# INTERFACE.net
KiCad netlist of a schematic drawn in EAGLE
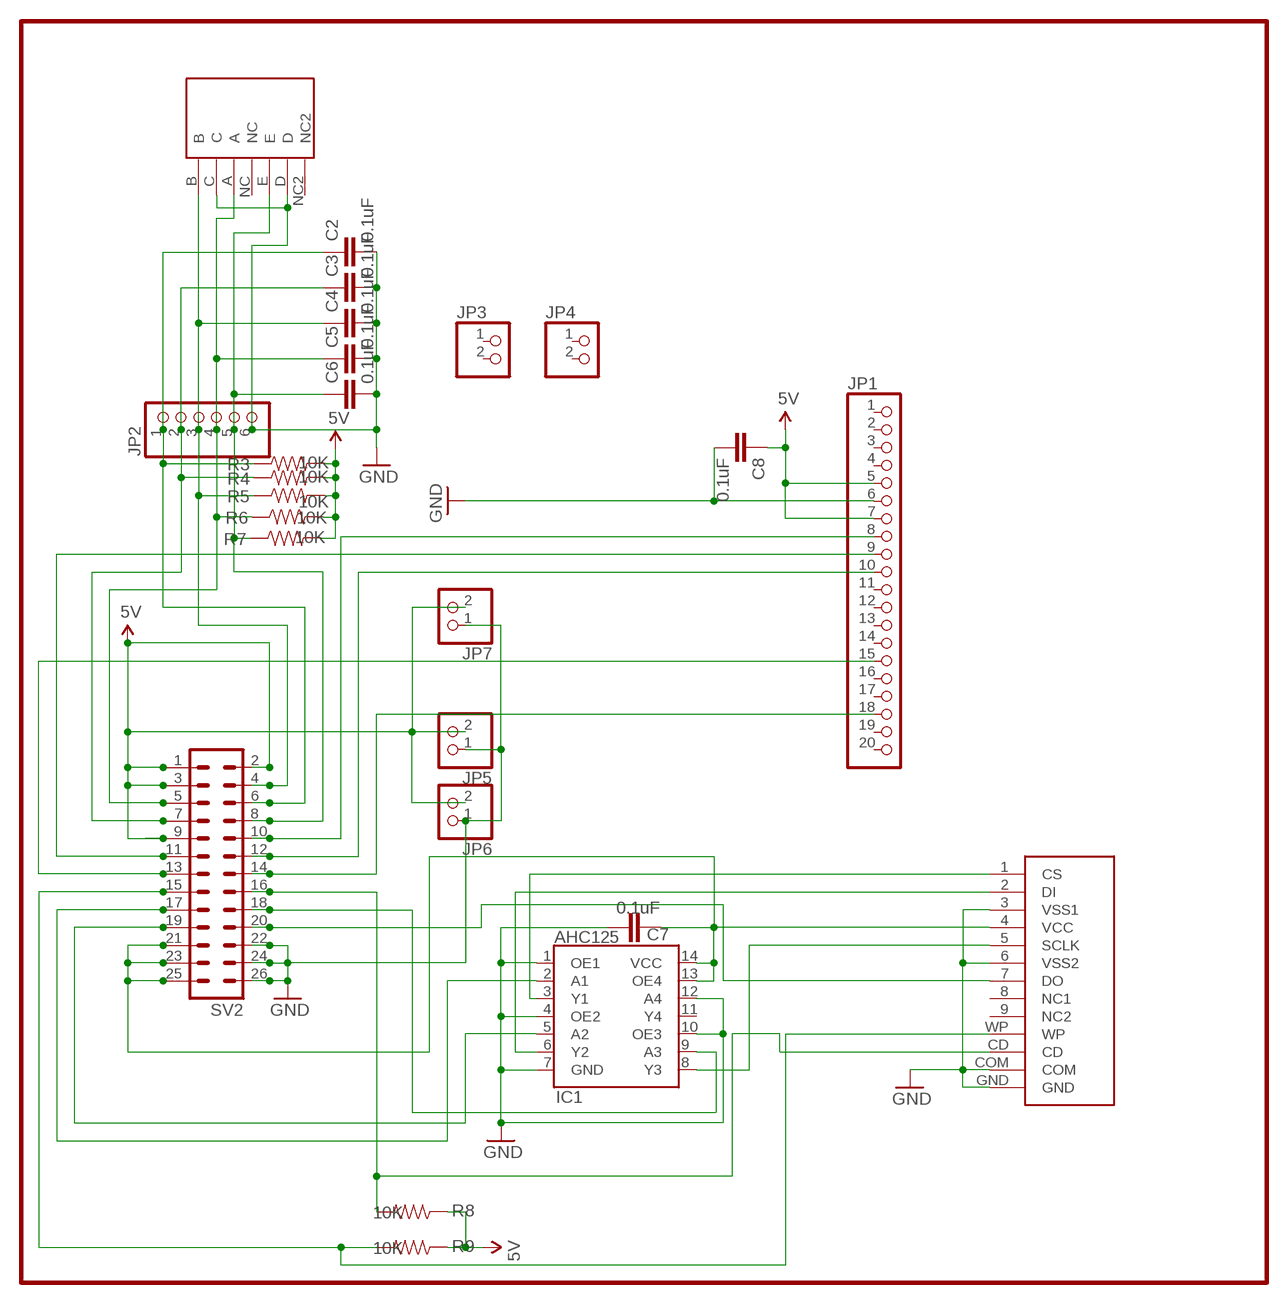
[diagram p0: schematic, sheet 1]

(export (version "E")
  (design (tool "Eeschema 10.0.6"))
  (components
    (comp (ref "C2")
      (value "0.1uF")
      (footprint "eagle-import:0805")
      (libsource (lib "eagle-import") (part "CAP0805"))
    )
    (comp (ref "C3")
      (value "0.1uF")
      (footprint "eagle-import:0805")
      (libsource (lib "eagle-import") (part "CAP0805"))
    )
    (comp (ref "C4")
      (value "0.1uF")
      (footprint "eagle-import:0805")
      (libsource (lib "eagle-import") (part "CAP0805"))
    )
    (comp (ref "C5")
      (value "0.1uF")
      (footprint "eagle-import:0805")
      (libsource (lib "eagle-import") (part "CAP0805"))
    )
    (comp (ref "C6")
      (value "0.1uF")
      (footprint "eagle-import:0805")
      (libsource (lib "eagle-import") (part "CAP0805"))
    )
    (comp (ref "C7")
      (value "0.1uF")
      (footprint "eagle-import:0805")
      (libsource (lib "eagle-import") (part "CAP0805"))
    )
    (comp (ref "C8")
      (value "0.1uF")
      (footprint "eagle-import:0805")
      (libsource (lib "eagle-import") (part "CAP0805"))
    )
    (comp (ref "IC1")
      (value "AHC125")
      (footprint "eagle-import:DIN14")
      (libsource (lib "eagle-import") (part "AHC125"))
    )
    (comp (ref "JP1")
      (value "PINHD-1X20")
      (footprint "eagle-import:1X20")
      (libsource (lib "eagle-import") (part "PINHD-1X20"))
    )
    (comp (ref "JP2")
      (value "PINHD-1X6")
      (footprint "eagle-import:1X06")
      (libsource (lib "eagle-import") (part "PINHD-1X6"))
    )
    (comp (ref "JP3")
      (value "PINHD-1X2")
      (footprint "eagle-import:1X02")
      (libsource (lib "eagle-import") (part "PINHD-1X2"))
    )
    (comp (ref "JP4")
      (value "PINHD-1X2")
      (footprint "eagle-import:1X02")
      (libsource (lib "eagle-import") (part "PINHD-1X2"))
    )
    (comp (ref "JP5")
      (value "PINHD-1X2")
      (footprint "eagle-import:1X02")
      (libsource (lib "eagle-import") (part "PINHD-1X2"))
    )
    (comp (ref "JP6")
      (value "PINHD-1X2")
      (footprint "eagle-import:1X02")
      (libsource (lib "eagle-import") (part "PINHD-1X2"))
    )
    (comp (ref "JP7")
      (value "PINHD-1X2")
      (footprint "eagle-import:1X02")
      (libsource (lib "eagle-import") (part "PINHD-1X2"))
    )
    (comp (ref "Q2")
      (value "SDCARD")
      (footprint "eagle-import:SDCARD")
      (libsource (lib "eagle-import") (part "SDCARD"))
    )
    (comp (ref "R3")
      (value "10K")
      (footprint "eagle-import:0805")
      (libsource (lib "eagle-import") (part "RESISTOR"))
    )
    (comp (ref "R4")
      (value "10K")
      (footprint "eagle-import:0805")
      (libsource (lib "eagle-import") (part "RESISTOR"))
    )
    (comp (ref "R5")
      (value "10K")
      (footprint "eagle-import:0805")
      (libsource (lib "eagle-import") (part "RESISTOR"))
    )
    (comp (ref "R6")
      (value "10K")
      (footprint "eagle-import:0805")
      (libsource (lib "eagle-import") (part "RESISTOR"))
    )
    (comp (ref "R7")
      (value "10K")
      (footprint "eagle-import:0805")
      (libsource (lib "eagle-import") (part "RESISTOR"))
    )
    (comp (ref "R8")
      (value "10K")
      (footprint "eagle-import:0805")
      (libsource (lib "eagle-import") (part "RESISTOR"))
    )
    (comp (ref "R9")
      (value "10K")
      (footprint "eagle-import:0805")
      (libsource (lib "eagle-import") (part "RESISTOR"))
    )
    (comp (ref "S2")
      (value "DJFS")
      (footprint "eagle-import:PIN5")
      (libsource (lib "eagle-import") (part "DJFS"))
    )
    (comp (ref "SV2")
      (value "ML26L")
      (footprint "eagle-import:ML26L")
      (libsource (lib "eagle-import") (part "ML26L"))
    )
  )
  (nets
    (net (code "1") (name "5V") (class "Default")
      (node (ref "C8") (pin "1") (pinfunction "1_1") (pintype "passive"))
      (node (ref "JP1") (pin "5") (pinfunction "5_5") (pintype "passive"))
      (node (ref "JP1") (pin "7") (pinfunction "7_7") (pintype "passive"))
      (node (ref "JP5") (pin "2") (pinfunction "2_2") (pintype "passive"))
      (node (ref "JP6") (pin "2") (pinfunction "2_2") (pintype "passive"))
      (node (ref "JP7") (pin "2") (pinfunction "2_2") (pintype "passive"))
      (node (ref "R3") (pin "2") (pinfunction "2_2") (pintype "passive"))
      (node (ref "R4") (pin "2") (pinfunction "2_2") (pintype "passive"))
      (node (ref "R5") (pin "2") (pinfunction "2_2") (pintype "passive"))
      (node (ref "R6") (pin "2") (pinfunction "2_2") (pintype "passive"))
      (node (ref "R7") (pin "2") (pinfunction "2_2") (pintype "passive"))
      (node (ref "R8") (pin "1") (pinfunction "1_1") (pintype "passive"))
      (node (ref "R9") (pin "1") (pinfunction "1_1") (pintype "passive"))
      (node (ref "SV2") (pin "1") (pinfunction "1_1") (pintype "passive"))
      (node (ref "SV2") (pin "2") (pinfunction "2_2") (pintype "passive"))
      (node (ref "SV2") (pin "3") (pinfunction "3_3") (pintype "passive"))
      (node (ref "SV2") (pin "9") (pinfunction "9_9") (pintype "passive"))
    )
    (net (code "2") (name "GND") (class "Default")
      (node (ref "C2") (pin "2") (pinfunction "2_2") (pintype "passive"))
      (node (ref "C3") (pin "2") (pinfunction "2_2") (pintype "passive"))
      (node (ref "C4") (pin "2") (pinfunction "2_2") (pintype "passive"))
      (node (ref "C5") (pin "2") (pinfunction "2_2") (pintype "passive"))
      (node (ref "C6") (pin "2") (pinfunction "2_2") (pintype "passive"))
      (node (ref "C7") (pin "2") (pinfunction "2_2") (pintype "passive"))
      (node (ref "C8") (pin "2") (pinfunction "2_2") (pintype "passive"))
      (node (ref "IC1") (pin "1") (pinfunction "OE1_1") (pintype "input"))
      (node (ref "IC1") (pin "10") (pinfunction "OE3_10") (pintype "input"))
      (node (ref "IC1") (pin "12") (pinfunction "A4_12") (pintype "input"))
      (node (ref "IC1") (pin "4") (pinfunction "OE2_4") (pintype "input"))
      (node (ref "IC1") (pin "7") (pinfunction "GND_7") (pintype "power_in"))
      (node (ref "JP1") (pin "6") (pinfunction "6_6") (pintype "passive"))
      (node (ref "JP2") (pin "6") (pinfunction "6_6") (pintype "passive"))
      (node (ref "JP5") (pin "1") (pinfunction "1_1") (pintype "passive"))
      (node (ref "JP6") (pin "1") (pinfunction "1_1") (pintype "passive"))
      (node (ref "JP7") (pin "1") (pinfunction "1_1") (pintype "passive"))
      (node (ref "Q2") (pin "3") (pinfunction "VSS1_3") (pintype "bidirectional"))
      (node (ref "Q2") (pin "6") (pinfunction "VSS2_6") (pintype "bidirectional"))
      (node (ref "Q2") (pin "COM") (pinfunction "COM_COM") (pintype "bidirectional"))
      (node (ref "Q2") (pin "GND") (pinfunction "GND_GND") (pintype "power_in"))
      (node (ref "S2") (pin "C") (pinfunction "C_C") (pintype "bidirectional"))
      (node (ref "S2") (pin "D") (pinfunction "D_D") (pintype "bidirectional"))
      (node (ref "SV2") (pin "22") (pinfunction "22_22") (pintype "passive"))
      (node (ref "SV2") (pin "24") (pinfunction "24_24") (pintype "passive"))
      (node (ref "SV2") (pin "26") (pinfunction "26_26") (pintype "passive"))
    )
    (net (code "3") (name "Net-(C2-Pad1)") (class "Default")
      (node (ref "C2") (pin "1") (pinfunction "1_1") (pintype "passive"))
      (node (ref "JP2") (pin "1") (pinfunction "1_1") (pintype "passive"))
      (node (ref "R3") (pin "1") (pinfunction "1_1") (pintype "passive"))
      (node (ref "SV2") (pin "6") (pinfunction "6_6") (pintype "passive"))
    )
    (net (code "4") (name "Net-(C3-Pad1)") (class "Default")
      (node (ref "C3") (pin "1") (pinfunction "1_1") (pintype "passive"))
      (node (ref "JP2") (pin "2") (pinfunction "2_2") (pintype "passive"))
      (node (ref "R4") (pin "1") (pinfunction "1_1") (pintype "passive"))
      (node (ref "SV2") (pin "7") (pinfunction "7_7") (pintype "passive"))
    )
    (net (code "5") (name "Net-(C4-Pad1)") (class "Default")
      (node (ref "C4") (pin "1") (pinfunction "1_1") (pintype "passive"))
      (node (ref "JP2") (pin "3") (pinfunction "3_3") (pintype "passive"))
      (node (ref "R5") (pin "1") (pinfunction "1_1") (pintype "passive"))
      (node (ref "S2") (pin "B") (pinfunction "B_B") (pintype "bidirectional"))
      (node (ref "SV2") (pin "4") (pinfunction "4_4") (pintype "passive"))
    )
    (net (code "6") (name "Net-(C5-Pad1)") (class "Default")
      (node (ref "C5") (pin "1") (pinfunction "1_1") (pintype "passive"))
      (node (ref "JP2") (pin "4") (pinfunction "4_4") (pintype "passive"))
      (node (ref "R6") (pin "1") (pinfunction "1_1") (pintype "passive"))
      (node (ref "S2") (pin "A") (pinfunction "A_A") (pintype "bidirectional"))
      (node (ref "SV2") (pin "5") (pinfunction "5_5") (pintype "passive"))
    )
    (net (code "7") (name "Net-(C6-Pad1)") (class "Default")
      (node (ref "C6") (pin "1") (pinfunction "1_1") (pintype "passive"))
      (node (ref "JP2") (pin "5") (pinfunction "5_5") (pintype "passive"))
      (node (ref "R7") (pin "1") (pinfunction "1_1") (pintype "passive"))
      (node (ref "S2") (pin "E") (pinfunction "E_E") (pintype "bidirectional"))
      (node (ref "SV2") (pin "8") (pinfunction "8_8") (pintype "passive"))
    )
    (net (code "8") (name "Net-(IC1-A1)") (class "Default")
      (node (ref "IC1") (pin "2") (pinfunction "A1_2") (pintype "input"))
      (node (ref "SV2") (pin "17") (pinfunction "17_17") (pintype "passive"))
    )
    (net (code "9") (name "Net-(IC1-A2)") (class "Default")
      (node (ref "IC1") (pin "5") (pinfunction "A2_5") (pintype "input"))
      (node (ref "SV2") (pin "19") (pinfunction "19_19") (pintype "passive"))
    )
    (net (code "10") (name "Net-(IC1-A3)") (class "Default")
      (node (ref "IC1") (pin "9") (pinfunction "A3_9") (pintype "input"))
      (node (ref "SV2") (pin "18") (pinfunction "18_18") (pintype "passive"))
    )
    (net (code "11") (name "Net-(IC1-OE4)") (class "Default")
      (node (ref "C7") (pin "1") (pinfunction "1_1") (pintype "passive"))
      (node (ref "IC1") (pin "13") (pinfunction "OE4_13") (pintype "input"))
      (node (ref "IC1") (pin "14") (pinfunction "VCC_14") (pintype "power_in"))
      (node (ref "Q2") (pin "4") (pinfunction "VCC_4") (pintype "power_in"))
      (node (ref "SV2") (pin "21") (pinfunction "21_21") (pintype "passive"))
      (node (ref "SV2") (pin "23") (pinfunction "23_23") (pintype "passive"))
      (node (ref "SV2") (pin "25") (pinfunction "25_25") (pintype "passive"))
    )
    (net (code "12") (name "Net-(IC1-Y1)") (class "Default")
      (node (ref "IC1") (pin "3") (pinfunction "Y1_3") (pintype "output"))
      (node (ref "Q2") (pin "1") (pinfunction "CS_1") (pintype "bidirectional"))
    )
    (net (code "13") (name "Net-(IC1-Y2)") (class "Default")
      (node (ref "IC1") (pin "6") (pinfunction "Y2_6") (pintype "output"))
      (node (ref "Q2") (pin "2") (pinfunction "DI_2") (pintype "bidirectional"))
    )
    (net (code "14") (name "Net-(IC1-Y3)") (class "Default")
      (node (ref "IC1") (pin "8") (pinfunction "Y3_8") (pintype "output"))
      (node (ref "Q2") (pin "5") (pinfunction "SCLK_5") (pintype "bidirectional"))
    )
    (net (code "15") (name "Net-(JP1-Pad8)") (class "Default")
      (node (ref "JP1") (pin "8") (pinfunction "8_8") (pintype "passive"))
      (node (ref "SV2") (pin "10") (pinfunction "10_10") (pintype "passive"))
    )
    (net (code "16") (name "Net-(JP1-Pad9)") (class "Default")
      (node (ref "JP1") (pin "9") (pinfunction "9_9") (pintype "passive"))
      (node (ref "SV2") (pin "11") (pinfunction "11_11") (pintype "passive"))
    )
    (net (code "17") (name "Net-(JP1-Pad10)") (class "Default")
      (node (ref "JP1") (pin "10") (pinfunction "10_10") (pintype "passive"))
      (node (ref "SV2") (pin "12") (pinfunction "12_12") (pintype "passive"))
    )
    (net (code "18") (name "Net-(JP1-Pad15)") (class "Default")
      (node (ref "JP1") (pin "15") (pinfunction "15_15") (pintype "passive"))
      (node (ref "SV2") (pin "13") (pinfunction "13_13") (pintype "passive"))
    )
    (net (code "19") (name "Net-(JP1-Pad18)") (class "Default")
      (node (ref "JP1") (pin "18") (pinfunction "18_18") (pintype "passive"))
      (node (ref "SV2") (pin "14") (pinfunction "14_14") (pintype "passive"))
    )
    (net (code "20") (name "Net-(Q2-DO)") (class "Default")
      (node (ref "Q2") (pin "7") (pinfunction "DO_7") (pintype "bidirectional"))
      (node (ref "SV2") (pin "20") (pinfunction "20_20") (pintype "passive"))
    )
    (net (code "21") (name "Net-(Q2-PadCD)") (class "Default")
      (node (ref "Q2") (pin "CD") (pinfunction "CD_CD") (pintype "bidirectional"))
      (node (ref "R8") (pin "2") (pinfunction "2_2") (pintype "passive"))
      (node (ref "SV2") (pin "16") (pinfunction "16_16") (pintype "passive"))
    )
    (net (code "22") (name "Net-(Q2-PadWP)") (class "Default")
      (node (ref "Q2") (pin "WP") (pinfunction "WP_WP") (pintype "bidirectional"))
      (node (ref "R9") (pin "2") (pinfunction "2_2") (pintype "passive"))
      (node (ref "SV2") (pin "15") (pinfunction "15_15") (pintype "passive"))
    )
    (net (code "23") (name "unconnected-(IC1-Y4-Pad11)") (class "Default")
      (node (ref "IC1") (pin "11") (pinfunction "Y4_11") (pintype "output"))
    )
    (net (code "24") (name "unconnected-(JP1-Pad1)") (class "Default")
      (node (ref "JP1") (pin "1") (pinfunction "1_1") (pintype "passive"))
    )
    (net (code "25") (name "unconnected-(JP1-Pad2)") (class "Default")
      (node (ref "JP1") (pin "2") (pinfunction "2_2") (pintype "passive"))
    )
    (net (code "26") (name "unconnected-(JP1-Pad3)") (class "Default")
      (node (ref "JP1") (pin "3") (pinfunction "3_3") (pintype "passive"))
    )
    (net (code "27") (name "unconnected-(JP1-Pad4)") (class "Default")
      (node (ref "JP1") (pin "4") (pinfunction "4_4") (pintype "passive"))
    )
    (net (code "28") (name "unconnected-(JP1-Pad11)") (class "Default")
      (node (ref "JP1") (pin "11") (pinfunction "11_11") (pintype "passive"))
    )
    (net (code "29") (name "unconnected-(JP1-Pad12)") (class "Default")
      (node (ref "JP1") (pin "12") (pinfunction "12_12") (pintype "passive"))
    )
    (net (code "30") (name "unconnected-(JP1-Pad13)") (class "Default")
      (node (ref "JP1") (pin "13") (pinfunction "13_13") (pintype "passive"))
    )
    (net (code "31") (name "unconnected-(JP1-Pad14)") (class "Default")
      (node (ref "JP1") (pin "14") (pinfunction "14_14") (pintype "passive"))
    )
    (net (code "32") (name "unconnected-(JP1-Pad16)") (class "Default")
      (node (ref "JP1") (pin "16") (pinfunction "16_16") (pintype "passive"))
    )
    (net (code "33") (name "unconnected-(JP1-Pad17)") (class "Default")
      (node (ref "JP1") (pin "17") (pinfunction "17_17") (pintype "passive"))
    )
    (net (code "34") (name "unconnected-(JP1-Pad19)") (class "Default")
      (node (ref "JP1") (pin "19") (pinfunction "19_19") (pintype "passive"))
    )
    (net (code "35") (name "unconnected-(JP1-Pad20)") (class "Default")
      (node (ref "JP1") (pin "20") (pinfunction "20_20") (pintype "passive"))
    )
    (net (code "36") (name "unconnected-(JP3-Pad1)") (class "Default")
      (node (ref "JP3") (pin "1") (pinfunction "1_1") (pintype "passive"))
    )
    (net (code "37") (name "unconnected-(JP3-Pad2)") (class "Default")
      (node (ref "JP3") (pin "2") (pinfunction "2_2") (pintype "passive"))
    )
    (net (code "38") (name "unconnected-(JP4-Pad1)") (class "Default")
      (node (ref "JP4") (pin "1") (pinfunction "1_1") (pintype "passive"))
    )
    (net (code "39") (name "unconnected-(JP4-Pad2)") (class "Default")
      (node (ref "JP4") (pin "2") (pinfunction "2_2") (pintype "passive"))
    )
    (net (code "40") (name "unconnected-(Q2-NC1-Pad8)") (class "Default")
      (node (ref "Q2") (pin "8") (pinfunction "NC1_8") (pintype "bidirectional"))
    )
    (net (code "41") (name "unconnected-(Q2-NC2-Pad9)") (class "Default")
      (node (ref "Q2") (pin "9") (pinfunction "NC2_9") (pintype "bidirectional"))
    )
    (net (code "42") (name "unconnected-(S2-PadNC)") (class "Default")
      (node (ref "S2") (pin "NC") (pinfunction "NC_NC") (pintype "no_connect"))
    )
    (net (code "43") (name "unconnected-(S2-PadNC2)") (class "Default")
      (node (ref "S2") (pin "NC2") (pinfunction "NC2_NC2") (pintype "no_connect"))
    )
  )
)
